# 1-Schematic_CessnaCitationX_Main_ESP32.net
KiCad netlist of a schematic drawn in EasyEDA
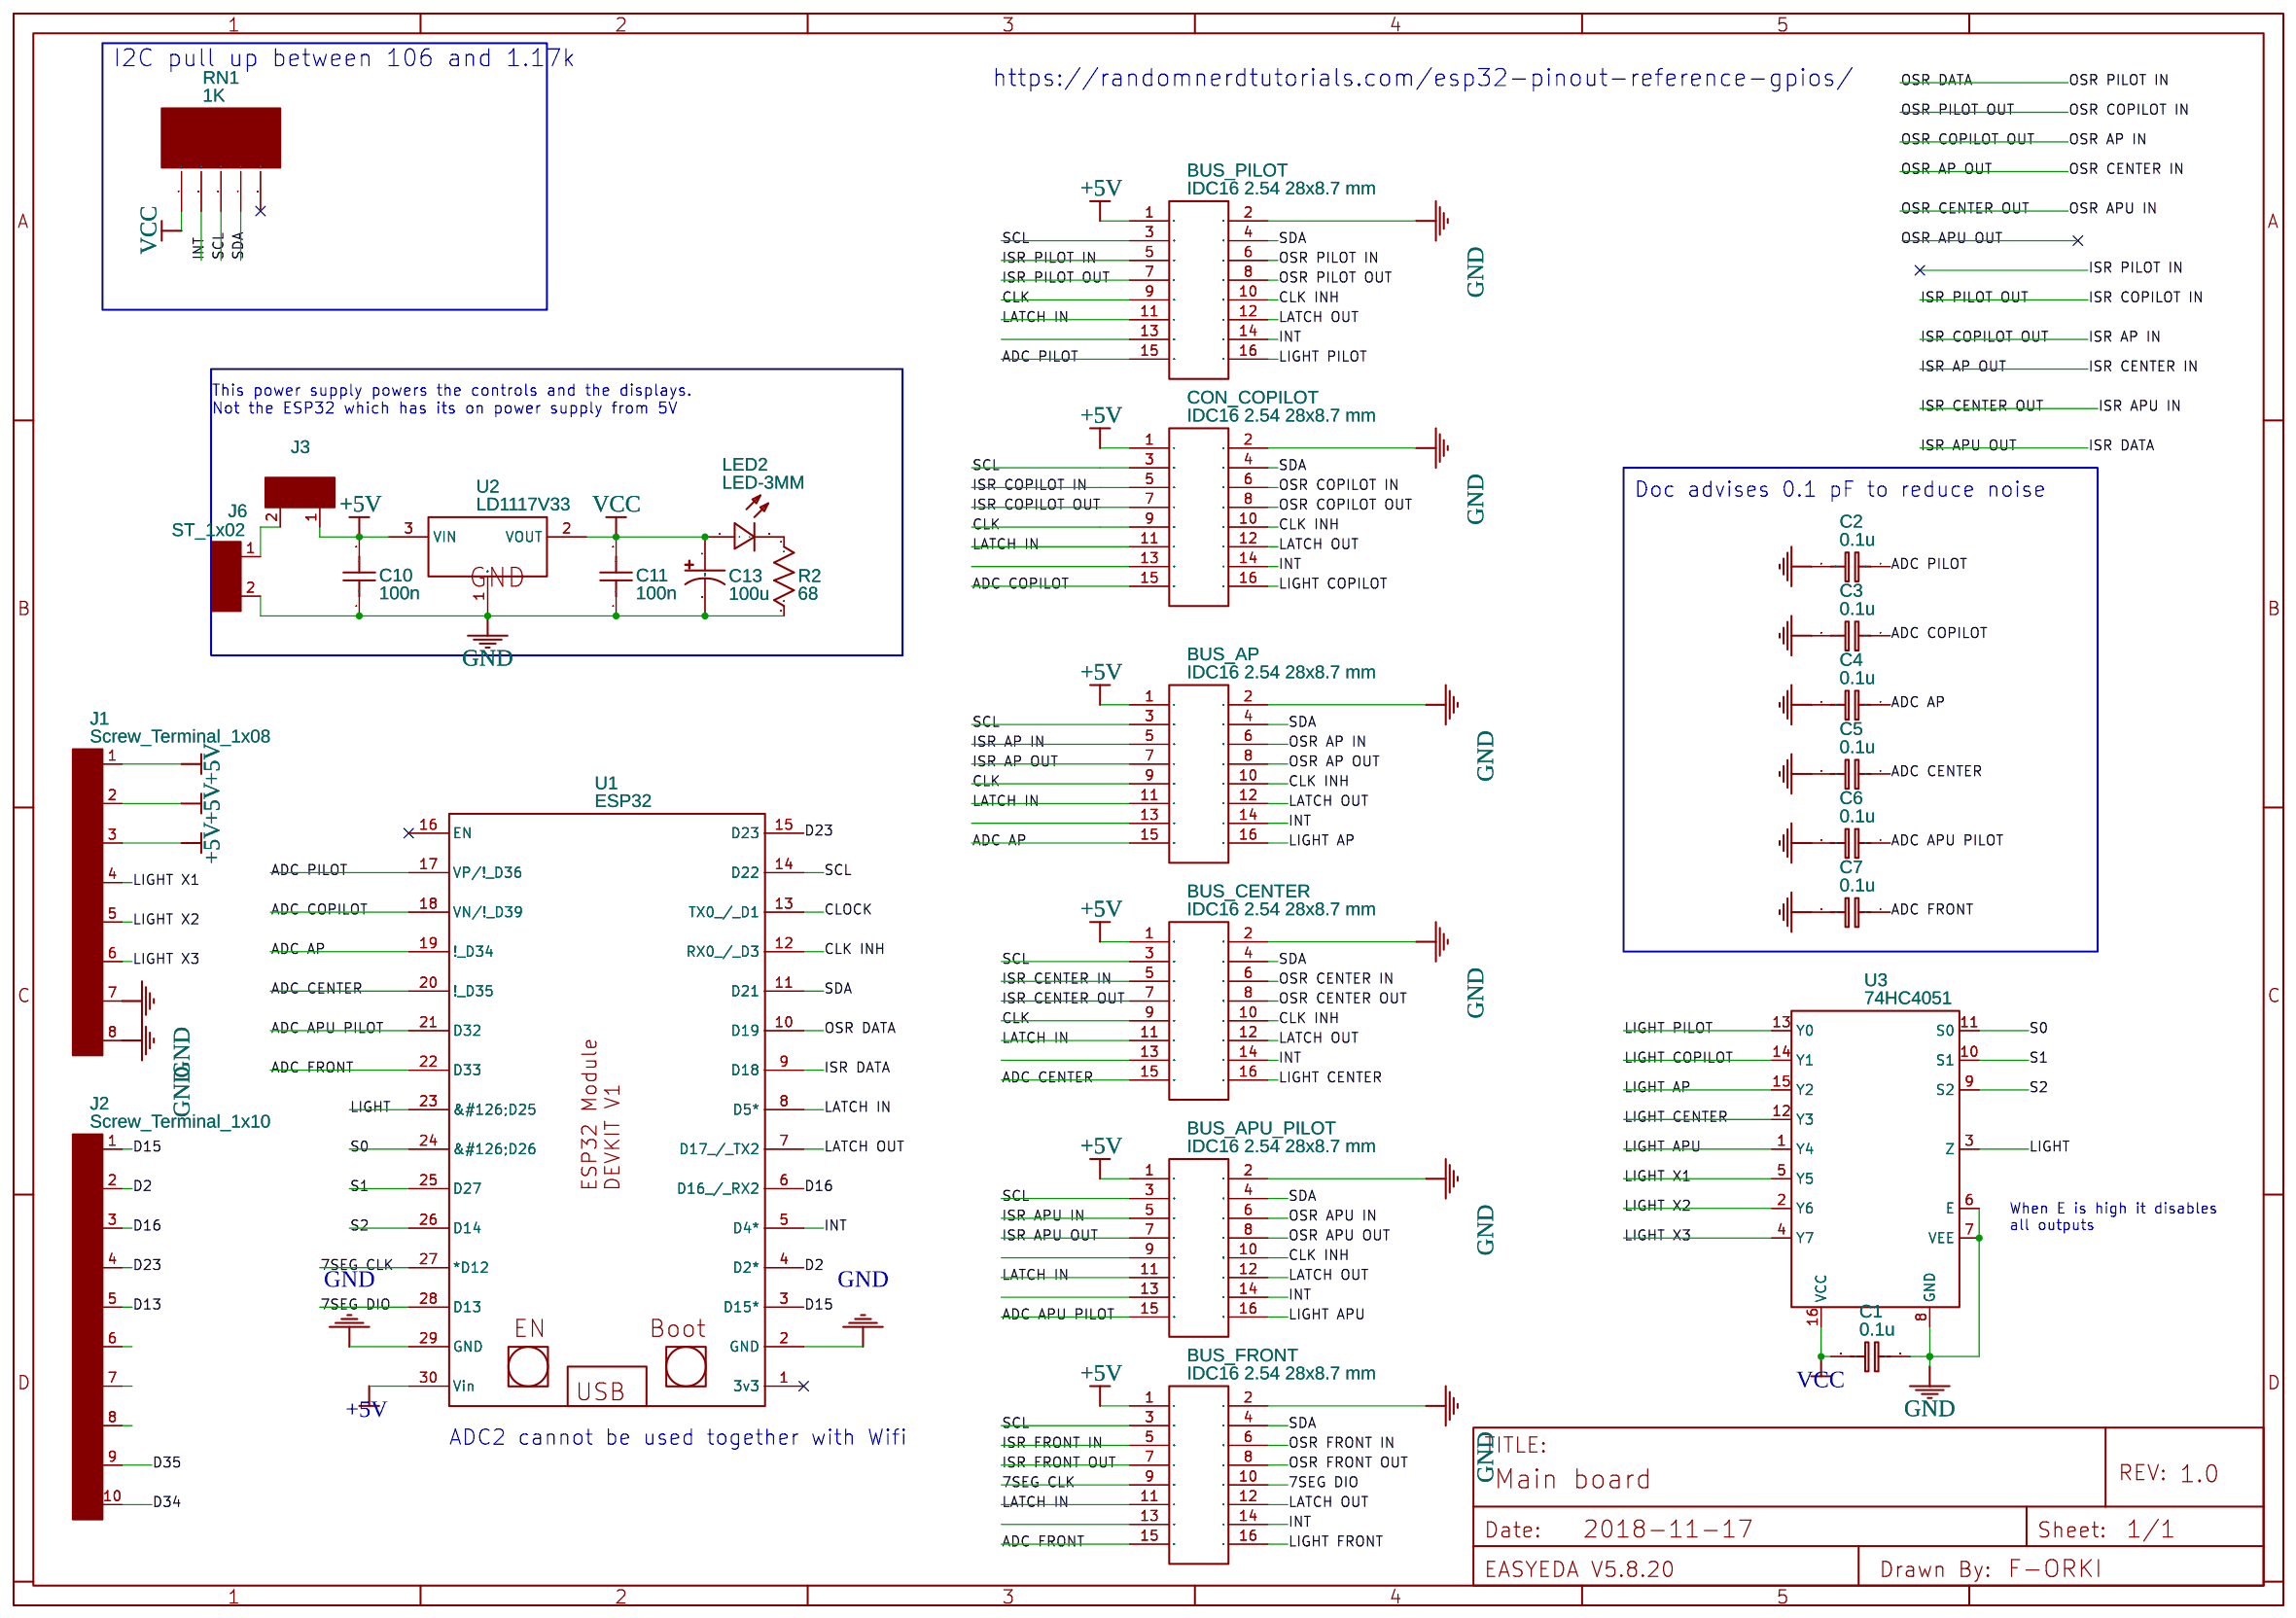
[diagram p0: schematic sheet]

(export (version "E")
  (design (tool "Eeschema 10.0.6"))
  (components
    (comp (ref "BUS_AP")
      (value "IDC16 2.54 28x8.7 mm")
      (fields (field (name "BOM_Manufacturer Part") "?"))
      (libsource (lib "") (part "Unknown_565_430"))
    )
    (comp (ref "BUS_APU_PILOT")
      (value "IDC16 2.54 28x8.7 mm")
      (fields (field (name "BOM_Manufacturer Part") "?"))
      (libsource (lib "") (part "Unknown_565_670"))
    )
    (comp (ref "BUS_CENTER")
      (value "IDC16 2.54 28x8.7 mm")
      (fields (field (name "BOM_Manufacturer Part") "?"))
      (libsource (lib "") (part "Unknown_565_550"))
    )
    (comp (ref "BUS_FRONT")
      (value "IDC16 2.54 28x8.7 mm")
      (fields (field (name "BOM_Manufacturer Part") "?"))
      (libsource (lib "") (part "Unknown_565_785"))
    )
    (comp (ref "BUS_PILOT")
      (value "IDC16 2.54 28x8.7 mm")
      (fields (field (name "BOM_Manufacturer Part") "?"))
      (libsource (lib "") (part "Unknown_565_185"))
    )
    (comp (ref "C1")
      (value "0.1u")
      (fields (field (name "BOM_Manufacturer Part") "?"))
      (libsource (lib "") (part "Cap_RAD-0.1_EU"))
    )
    (comp (ref "C2")
      (value "0.1u")
      (fields (field (name "BOM_Manufacturer Part") "?"))
      (libsource (lib "") (part "Cap_RAD-0.1_EU_1"))
    )
    (comp (ref "C3")
      (value "0.1u")
      (fields (field (name "BOM_Manufacturer Part") "?"))
      (libsource (lib "") (part "Cap_RAD-0.1_EU_1"))
    )
    (comp (ref "C4")
      (value "0.1u")
      (fields (field (name "BOM_Manufacturer Part") "?"))
      (libsource (lib "") (part "Cap_RAD-0.1_EU_1"))
    )
    (comp (ref "C5")
      (value "0.1u")
      (fields (field (name "BOM_Manufacturer Part") "?"))
      (libsource (lib "") (part "Cap_RAD-0.1_EU_1"))
    )
    (comp (ref "C6")
      (value "0.1u")
      (fields (field (name "BOM_Manufacturer Part") "?"))
      (libsource (lib "") (part "Cap_RAD-0.1_EU_1"))
    )
    (comp (ref "C7")
      (value "0.1u")
      (fields (field (name "BOM_Manufacturer Part") "?"))
      (libsource (lib "") (part "Cap_RAD-0.1_EU_1"))
    )
    (comp (ref "C10")
      (value "100n")
      (fields (field (name "BOM_Manufacturer Part") "?"))
      (libsource (lib "") (part "Cap_RAD-0.1_US"))
    )
    (comp (ref "C11")
      (value "100n")
      (fields (field (name "BOM_Manufacturer Part") "?"))
      (libsource (lib "") (part "Cap_RAD-0.1_US"))
    )
    (comp (ref "C13")
      (value "100u")
      (fields (field (name "BOM_Manufacturer Part") "?"))
      (libsource (lib "") (part "Cap_Electrolytic(TH)_D3.0XF1.5_US"))
    )
    (comp (ref "CON_COPILOT")
      (value "IDC16 2.54 28x8.7 mm")
      (fields (field (name "BOM_Manufacturer Part") "?"))
      (libsource (lib "") (part "Unknown_565_300"))
    )
    (comp (ref "J1")
      (value "Screw_Terminal_1x08")
      (fields (field (name "BOM_Manufacturer Part") "?"))
      (libsource (lib "") (part "Unknown_45_450"))
    )
    (comp (ref "J2")
      (value "Screw_Terminal_1x10")
      (fields (field (name "BOM_Manufacturer Part") "?"))
      (libsource (lib "") (part "Unknown_45_665"))
    )
    (comp (ref "J3")
      (value "ST_1x02")
      (fields (field (name "BOM_Manufacturer Part") "?"))
      (libsource (lib "") (part "Unknown_155_250"))
    )
    (comp (ref "J6")
      (value "ST_1x02")
      (fields (field (name "BOM_Manufacturer Part") "?"))
      (libsource (lib "") (part "Unknown_115_275"))
    )
    (comp (ref "LED2")
      (value "LED-3MM")
      (fields
        (field (name "BOM_Manufacturer Part") "204-10SURD/S530-A3")
        (field (name "BOM_Supplier Part") "C99772")
      )
      (libsource (lib "") (part "Unknown_370_260"))
    )
    (comp (ref "R2")
      (value "68")
      (fields (field (name "BOM_Manufacturer Part") "?"))
      (libsource (lib "") (part "Res_AXIAL-0.3(1/8W)_US"))
    )
    (comp (ref "RN1")
      (value "1K")
      (fields (field (name "BOM_Manufacturer Part") "A05-102JP") (field (name "BOM_Supplier Part") "C11389"))
      (libsource (lib "") (part "A05-102JP"))
    )
    (comp (ref "U1")
      (value "ESP32")
      (fields (field (name "BOM_Manufacturer Part") "ESP32 DEV KIT V1"))
      (libsource (lib "") (part "Unknown_300_555"))
    )
    (comp (ref "U2")
      (value "LD1117V33")
      (fields (field (name "BOM_Supplier Part") "C283467"))
      (libsource (lib "") (part "Unknown_240_285"))
    )
    (comp (ref "U3")
      (value "74HC4051")
      (fields (field (name "BOM_Manufacturer Part") "?"))
      (libsource (lib "") (part "Unknown_945_575"))
    )
  )
  (nets
    (net (code "1") (name "+5V") (class "Default")
      (node (ref "BUS_AP") (pin "1") (pinfunction "P1_1") (pintype "unspecified"))
      (node (ref "BUS_APU_PILOT") (pin "1") (pinfunction "P1_1") (pintype "unspecified"))
      (node (ref "BUS_CENTER") (pin "1") (pinfunction "P1_1") (pintype "unspecified"))
      (node (ref "BUS_FRONT") (pin "1") (pinfunction "P1_1") (pintype "unspecified"))
      (node (ref "BUS_PILOT") (pin "1") (pinfunction "P1_1") (pintype "unspecified"))
      (node (ref "C10") (pin "2") (pinfunction "2_2") (pintype "unspecified"))
      (node (ref "CON_COPILOT") (pin "1") (pinfunction "P1_1") (pintype "unspecified"))
      (node (ref "J1") (pin "1") (pintype "unspecified"))
      (node (ref "J1") (pin "2") (pintype "unspecified"))
      (node (ref "J1") (pin "3") (pintype "unspecified"))
      (node (ref "J3") (pin "1") (pintype "unspecified"))
      (node (ref "U1") (pin "30") (pinfunction "Vin_30") (pintype "passive"))
      (node (ref "U2") (pin "3") (pinfunction "VIN_3") (pintype "passive"))
    )
    (net (code "2") (name "/7SEG CLK") (class "Default")
      (node (ref "BUS_FRONT") (pin "9") (pinfunction "P9_9") (pintype "unspecified"))
      (node (ref "U1") (pin "27") (pinfunction "*D12_27") (pintype "unspecified"))
    )
    (net (code "3") (name "/7SEG DIO") (class "Default")
      (node (ref "BUS_FRONT") (pin "10") (pinfunction "P10_10") (pintype "unspecified"))
      (node (ref "U1") (pin "28") (pinfunction "D13_28") (pintype "bidirectional"))
    )
    (net (code "4") (name "/ADC AP") (class "Default")
      (node (ref "BUS_AP") (pin "15") (pinfunction "15_15") (pintype "unspecified"))
      (node (ref "C4") (pin "1") (pinfunction "1_1") (pintype "unspecified"))
      (node (ref "U1") (pin "19") (pinfunction "!_D34_19") (pintype "unspecified"))
    )
    (net (code "5") (name "/ADC APU PILOT") (class "Default")
      (node (ref "BUS_APU_PILOT") (pin "15") (pinfunction "15_15") (pintype "unspecified"))
      (node (ref "C6") (pin "1") (pinfunction "1_1") (pintype "unspecified"))
      (node (ref "U1") (pin "21") (pinfunction "D32_21") (pintype "unspecified"))
    )
    (net (code "6") (name "/ADC CENTER") (class "Default")
      (node (ref "BUS_CENTER") (pin "15") (pinfunction "15_15") (pintype "unspecified"))
      (node (ref "C5") (pin "1") (pinfunction "1_1") (pintype "unspecified"))
      (node (ref "U1") (pin "20") (pinfunction "!_D35_20") (pintype "unspecified"))
    )
    (net (code "7") (name "/ADC COPILOT") (class "Default")
      (node (ref "C3") (pin "1") (pinfunction "1_1") (pintype "unspecified"))
      (node (ref "CON_COPILOT") (pin "15") (pinfunction "15_15") (pintype "unspecified"))
      (node (ref "U1") (pin "18") (pinfunction "VN/!_D39_18") (pintype "unspecified"))
    )
    (net (code "8") (name "/ADC FRONT") (class "Default")
      (node (ref "BUS_FRONT") (pin "15") (pinfunction "15_15") (pintype "unspecified"))
      (node (ref "C7") (pin "1") (pinfunction "1_1") (pintype "unspecified"))
      (node (ref "U1") (pin "22") (pinfunction "D33_22") (pintype "unspecified"))
    )
    (net (code "9") (name "/ADC PILOT") (class "Default")
      (node (ref "BUS_PILOT") (pin "15") (pinfunction "15_15") (pintype "unspecified"))
      (node (ref "C2") (pin "1") (pinfunction "1_1") (pintype "unspecified"))
      (node (ref "U1") (pin "17") (pinfunction "VP/!_D36_17") (pintype "unspecified"))
    )
    (net (code "10") (name "/CLK") (class "Default")
      (node (ref "BUS_AP") (pin "9") (pinfunction "P9_9") (pintype "unspecified"))
      (node (ref "BUS_CENTER") (pin "9") (pinfunction "P9_9") (pintype "unspecified"))
      (node (ref "BUS_PILOT") (pin "9") (pinfunction "P9_9") (pintype "unspecified"))
      (node (ref "CON_COPILOT") (pin "9") (pinfunction "P9_9") (pintype "unspecified"))
    )
    (net (code "11") (name "/CLK INH") (class "Default")
      (node (ref "BUS_AP") (pin "10") (pinfunction "P10_10") (pintype "unspecified"))
      (node (ref "BUS_APU_PILOT") (pin "10") (pinfunction "P10_10") (pintype "unspecified"))
      (node (ref "BUS_CENTER") (pin "10") (pinfunction "P10_10") (pintype "unspecified"))
      (node (ref "BUS_PILOT") (pin "10") (pinfunction "P10_10") (pintype "unspecified"))
      (node (ref "CON_COPILOT") (pin "10") (pinfunction "P10_10") (pintype "unspecified"))
      (node (ref "U1") (pin "12") (pinfunction "RX0_/_D3_12") (pintype "bidirectional"))
    )
    (net (code "12") (name "/CLOCK") (class "Default")
      (node (ref "U1") (pin "13") (pinfunction "TX0_/_D1_13") (pintype "bidirectional"))
    )
    (net (code "13") (name "/D2") (class "Default")
      (node (ref "J2") (pin "2") (pintype "unspecified"))
      (node (ref "U1") (pin "4") (pinfunction "D2*_4") (pintype "bidirectional"))
    )
    (net (code "14") (name "/D13") (class "Default") (node (ref "J2") (pin "5") (pintype "unspecified")))
    (net (code "15") (name "/D15") (class "Default")
      (node (ref "J2") (pin "1") (pintype "unspecified"))
      (node (ref "U1") (pin "3") (pinfunction "D15*_3") (pintype "bidirectional"))
    )
    (net (code "16") (name "/D16") (class "Default")
      (node (ref "J2") (pin "3") (pintype "unspecified"))
      (node (ref "U1") (pin "6") (pinfunction "D16_/_RX2_6") (pintype "bidirectional"))
    )
    (net (code "17") (name "/D23") (class "Default")
      (node (ref "J2") (pin "4") (pintype "unspecified"))
      (node (ref "U1") (pin "15") (pinfunction "D23_15") (pintype "bidirectional"))
    )
    (net (code "18") (name "/D34") (class "Default") (node (ref "J2") (pin "10") (pintype "unspecified")))
    (net (code "19") (name "/D35") (class "Default") (node (ref "J2") (pin "9") (pintype "unspecified")))
    (net (code "20") (name "/INT") (class "Default")
      (node (ref "BUS_AP") (pin "14") (pinfunction "14_14") (pintype "unspecified"))
      (node (ref "BUS_APU_PILOT") (pin "14") (pinfunction "14_14") (pintype "unspecified"))
      (node (ref "BUS_CENTER") (pin "14") (pinfunction "14_14") (pintype "unspecified"))
      (node (ref "BUS_FRONT") (pin "14") (pinfunction "14_14") (pintype "unspecified"))
      (node (ref "BUS_PILOT") (pin "14") (pinfunction "14_14") (pintype "unspecified"))
      (node (ref "CON_COPILOT") (pin "14") (pinfunction "14_14") (pintype "unspecified"))
      (node (ref "RN1") (pin "2") (pinfunction "2_2") (pintype "input"))
      (node (ref "U1") (pin "5") (pinfunction "D4*_5") (pintype "bidirectional"))
    )
    (net (code "21") (name "/ISR AP IN") (class "Default")
      (node (ref "BUS_AP") (pin "5") (pinfunction "P5_5") (pintype "unspecified"))
      (node (ref "CON_COPILOT") (pin "7") (pinfunction "P7_7") (pintype "unspecified"))
    )
    (net (code "22") (name "/ISR AP OUT") (class "Default")
      (node (ref "BUS_AP") (pin "7") (pinfunction "P7_7") (pintype "unspecified"))
      (node (ref "BUS_CENTER") (pin "5") (pinfunction "P5_5") (pintype "unspecified"))
    )
    (net (code "23") (name "/ISR APU IN") (class "Default")
      (node (ref "BUS_APU_PILOT") (pin "5") (pinfunction "P5_5") (pintype "unspecified"))
      (node (ref "BUS_CENTER") (pin "7") (pinfunction "P7_7") (pintype "unspecified"))
    )
    (net (code "24") (name "/ISR APU OUT") (class "Default")
      (node (ref "BUS_APU_PILOT") (pin "7") (pinfunction "P7_7") (pintype "unspecified"))
      (node (ref "U1") (pin "9") (pinfunction "D18_9") (pintype "unspecified"))
    )
    (net (code "25") (name "/ISR COPILOT IN") (class "Default")
      (node (ref "BUS_PILOT") (pin "7") (pinfunction "P7_7") (pintype "unspecified"))
      (node (ref "CON_COPILOT") (pin "5") (pinfunction "P5_5") (pintype "unspecified"))
    )
    (net (code "26") (name "/ISR FRONT IN") (class "Default")
      (node (ref "BUS_FRONT") (pin "5") (pinfunction "P5_5") (pintype "unspecified"))
    )
    (net (code "27") (name "/ISR FRONT OUT") (class "Default")
      (node (ref "BUS_FRONT") (pin "7") (pinfunction "P7_7") (pintype "unspecified"))
    )
    (net (code "28") (name "/ISR PILOT IN") (class "Default")
      (node (ref "BUS_PILOT") (pin "5") (pinfunction "P5_5") (pintype "unspecified"))
    )
    (net (code "29") (name "/LATCH IN") (class "Default")
      (node (ref "BUS_AP") (pin "11") (pinfunction "11_11") (pintype "unspecified"))
      (node (ref "BUS_APU_PILOT") (pin "11") (pinfunction "11_11") (pintype "unspecified"))
      (node (ref "BUS_CENTER") (pin "11") (pinfunction "11_11") (pintype "unspecified"))
      (node (ref "BUS_FRONT") (pin "11") (pinfunction "11_11") (pintype "unspecified"))
      (node (ref "BUS_PILOT") (pin "11") (pinfunction "11_11") (pintype "unspecified"))
      (node (ref "CON_COPILOT") (pin "11") (pinfunction "11_11") (pintype "unspecified"))
      (node (ref "U1") (pin "8") (pinfunction "D5*_8") (pintype "unspecified"))
    )
    (net (code "30") (name "/LATCH OUT") (class "Default")
      (node (ref "BUS_AP") (pin "12") (pinfunction "12_12") (pintype "unspecified"))
      (node (ref "BUS_APU_PILOT") (pin "12") (pinfunction "12_12") (pintype "unspecified"))
      (node (ref "BUS_CENTER") (pin "12") (pinfunction "12_12") (pintype "unspecified"))
      (node (ref "BUS_FRONT") (pin "12") (pinfunction "12_12") (pintype "unspecified"))
      (node (ref "BUS_PILOT") (pin "12") (pinfunction "12_12") (pintype "unspecified"))
      (node (ref "CON_COPILOT") (pin "12") (pinfunction "12_12") (pintype "unspecified"))
      (node (ref "U1") (pin "7") (pinfunction "D17_/_TX2_7") (pintype "bidirectional"))
    )
    (net (code "31") (name "/LIGHT") (class "Default")
      (node (ref "U1") (pin "23") (pinfunction "&#126;D25_23") (pintype "unspecified"))
      (node (ref "U3") (pin "3") (pinfunction "Z_3") (pintype "unspecified"))
    )
    (net (code "32") (name "/LIGHT AP") (class "Default")
      (node (ref "BUS_AP") (pin "16") (pinfunction "16_16") (pintype "unspecified"))
      (node (ref "U3") (pin "15") (pinfunction "Y2_15") (pintype "unspecified"))
    )
    (net (code "33") (name "/LIGHT APU") (class "Default")
      (node (ref "BUS_APU_PILOT") (pin "16") (pinfunction "16_16") (pintype "unspecified"))
      (node (ref "U3") (pin "1") (pinfunction "Y4_1") (pintype "unspecified"))
    )
    (net (code "34") (name "/LIGHT CENTER") (class "Default")
      (node (ref "BUS_CENTER") (pin "16") (pinfunction "16_16") (pintype "unspecified"))
      (node (ref "U3") (pin "12") (pinfunction "Y3_12") (pintype "unspecified"))
    )
    (net (code "35") (name "/LIGHT COPILOT") (class "Default")
      (node (ref "CON_COPILOT") (pin "16") (pinfunction "16_16") (pintype "unspecified"))
      (node (ref "U3") (pin "14") (pinfunction "Y1_14") (pintype "unspecified"))
    )
    (net (code "36") (name "/LIGHT FRONT") (class "Default")
      (node (ref "BUS_FRONT") (pin "16") (pinfunction "16_16") (pintype "unspecified"))
    )
    (net (code "37") (name "/LIGHT PILOT") (class "Default")
      (node (ref "BUS_PILOT") (pin "16") (pinfunction "16_16") (pintype "unspecified"))
      (node (ref "U3") (pin "13") (pinfunction "Y0_13") (pintype "unspecified"))
    )
    (net (code "38") (name "/LIGHT X1") (class "Default")
      (node (ref "J1") (pin "4") (pintype "unspecified"))
      (node (ref "U3") (pin "5") (pinfunction "Y5_5") (pintype "unspecified"))
    )
    (net (code "39") (name "/LIGHT X2") (class "Default")
      (node (ref "J1") (pin "5") (pintype "unspecified"))
      (node (ref "U3") (pin "2") (pinfunction "Y6_2") (pintype "unspecified"))
    )
    (net (code "40") (name "/LIGHT X3") (class "Default")
      (node (ref "J1") (pin "6") (pintype "unspecified"))
      (node (ref "U3") (pin "4") (pinfunction "Y7_4") (pintype "unspecified"))
    )
    (net (code "41") (name "/OSR AP IN") (class "Default")
      (node (ref "BUS_AP") (pin "6") (pinfunction "P6_6") (pintype "unspecified"))
      (node (ref "CON_COPILOT") (pin "8") (pinfunction "P8_8") (pintype "unspecified"))
    )
    (net (code "42") (name "/OSR AP OUT") (class "Default")
      (node (ref "BUS_AP") (pin "8") (pinfunction "P8_8") (pintype "unspecified"))
      (node (ref "BUS_CENTER") (pin "6") (pinfunction "P6_6") (pintype "unspecified"))
    )
    (net (code "43") (name "/OSR APU IN") (class "Default")
      (node (ref "BUS_APU_PILOT") (pin "6") (pinfunction "P6_6") (pintype "unspecified"))
      (node (ref "BUS_CENTER") (pin "8") (pinfunction "P8_8") (pintype "unspecified"))
    )
    (net (code "44") (name "/OSR APU OUT") (class "Default")
      (node (ref "BUS_APU_PILOT") (pin "8") (pinfunction "P8_8") (pintype "unspecified"))
    )
    (net (code "45") (name "/OSR COPILOT IN") (class "Default")
      (node (ref "BUS_PILOT") (pin "8") (pinfunction "P8_8") (pintype "unspecified"))
      (node (ref "CON_COPILOT") (pin "6") (pinfunction "P6_6") (pintype "unspecified"))
    )
    (net (code "46") (name "/OSR DATA") (class "Default")
      (node (ref "BUS_PILOT") (pin "6") (pinfunction "P6_6") (pintype "unspecified"))
      (node (ref "U1") (pin "10") (pinfunction "D19_10") (pintype "bidirectional"))
    )
    (net (code "47") (name "/OSR FRONT IN") (class "Default")
      (node (ref "BUS_FRONT") (pin "6") (pinfunction "P6_6") (pintype "unspecified"))
    )
    (net (code "48") (name "/OSR FRONT OUT") (class "Default")
      (node (ref "BUS_FRONT") (pin "8") (pinfunction "P8_8") (pintype "unspecified"))
    )
    (net (code "49") (name "/S0") (class "Default")
      (node (ref "U1") (pin "24") (pinfunction "&#126;D26_24") (pintype "unspecified"))
      (node (ref "U3") (pin "11") (pinfunction "S0_11") (pintype "unspecified"))
    )
    (net (code "50") (name "/S1") (class "Default")
      (node (ref "U1") (pin "25") (pinfunction "D27_25") (pintype "unspecified"))
      (node (ref "U3") (pin "10") (pinfunction "S1_10") (pintype "unspecified"))
    )
    (net (code "51") (name "/S2") (class "Default")
      (node (ref "U1") (pin "26") (pinfunction "D14_26") (pintype "unspecified"))
      (node (ref "U3") (pin "9") (pinfunction "S2_9") (pintype "unspecified"))
    )
    (net (code "52") (name "/SCL") (class "Default")
      (node (ref "BUS_AP") (pin "3") (pinfunction "P3_3") (pintype "unspecified"))
      (node (ref "BUS_APU_PILOT") (pin "3") (pinfunction "P3_3") (pintype "unspecified"))
      (node (ref "BUS_CENTER") (pin "3") (pinfunction "P3_3") (pintype "unspecified"))
      (node (ref "BUS_FRONT") (pin "3") (pinfunction "P3_3") (pintype "unspecified"))
      (node (ref "BUS_PILOT") (pin "3") (pinfunction "P3_3") (pintype "unspecified"))
      (node (ref "CON_COPILOT") (pin "3") (pinfunction "P3_3") (pintype "unspecified"))
      (node (ref "RN1") (pin "3") (pinfunction "3_3") (pintype "input"))
      (node (ref "U1") (pin "14") (pinfunction "D22_14") (pintype "bidirectional"))
    )
    (net (code "53") (name "/SDA") (class "Default")
      (node (ref "BUS_AP") (pin "4") (pinfunction "P4_4") (pintype "unspecified"))
      (node (ref "BUS_APU_PILOT") (pin "4") (pinfunction "P4_4") (pintype "unspecified"))
      (node (ref "BUS_CENTER") (pin "4") (pinfunction "P4_4") (pintype "unspecified"))
      (node (ref "BUS_FRONT") (pin "4") (pinfunction "P4_4") (pintype "unspecified"))
      (node (ref "BUS_PILOT") (pin "4") (pinfunction "P4_4") (pintype "unspecified"))
      (node (ref "CON_COPILOT") (pin "4") (pinfunction "P4_4") (pintype "unspecified"))
      (node (ref "RN1") (pin "4") (pinfunction "4_4") (pintype "input"))
      (node (ref "U1") (pin "11") (pinfunction "D21_11") (pintype "bidirectional"))
    )
    (net (code "54") (name "GND") (class "Default")
      (node (ref "BUS_AP") (pin "2") (pinfunction "P2_2") (pintype "unspecified"))
      (node (ref "BUS_APU_PILOT") (pin "2") (pinfunction "P2_2") (pintype "unspecified"))
      (node (ref "BUS_CENTER") (pin "2") (pinfunction "P2_2") (pintype "unspecified"))
      (node (ref "BUS_FRONT") (pin "2") (pinfunction "P2_2") (pintype "unspecified"))
      (node (ref "BUS_PILOT") (pin "2") (pinfunction "P2_2") (pintype "unspecified"))
      (node (ref "C1") (pin "1") (pinfunction "1_1") (pintype "unspecified"))
      (node (ref "C10") (pin "1") (pinfunction "1_1") (pintype "unspecified"))
      (node (ref "C11") (pin "1") (pinfunction "1_1") (pintype "unspecified"))
      (node (ref "C13") (pin "2") (pinfunction "2_2") (pintype "unspecified"))
      (node (ref "C2") (pin "2") (pinfunction "2_2") (pintype "unspecified"))
      (node (ref "C3") (pin "2") (pinfunction "2_2") (pintype "unspecified"))
      (node (ref "C4") (pin "2") (pinfunction "2_2") (pintype "unspecified"))
      (node (ref "C5") (pin "2") (pinfunction "2_2") (pintype "unspecified"))
      (node (ref "C6") (pin "2") (pinfunction "2_2") (pintype "unspecified"))
      (node (ref "C7") (pin "2") (pinfunction "2_2") (pintype "unspecified"))
      (node (ref "CON_COPILOT") (pin "2") (pinfunction "P2_2") (pintype "unspecified"))
      (node (ref "J1") (pin "7") (pintype "unspecified"))
      (node (ref "J1") (pin "8") (pintype "unspecified"))
      (node (ref "J6") (pin "2") (pintype "unspecified"))
      (node (ref "R2") (pin "2") (pinfunction "2_2") (pintype "unspecified"))
      (node (ref "U1") (pin "2") (pinfunction "GND_2") (pintype "passive"))
      (node (ref "U1") (pin "29") (pinfunction "GND_29") (pintype "passive"))
      (node (ref "U2") (pin "1") (pinfunction "GND_1") (pintype "unspecified"))
      (node (ref "U3") (pin "6") (pinfunction "E_6") (pintype "unspecified"))
      (node (ref "U3") (pin "7") (pinfunction "VEE_7") (pintype "unspecified"))
      (node (ref "U3") (pin "8") (pinfunction "GND_8") (pintype "unspecified"))
    )
    (net (code "55") (name "Net-(J3-Pad2)") (class "Default")
      (node (ref "J3") (pin "2") (pintype "unspecified"))
      (node (ref "J6") (pin "1") (pintype "unspecified"))
    )
    (net (code "56") (name "Net-(LED2--)") (class "Default")
      (node (ref "LED2") (pin "2") (pinfunction "-_2") (pintype "unspecified"))
      (node (ref "R2") (pin "1") (pinfunction "1_1") (pintype "unspecified"))
    )
    (net (code "57") (name "VCC") (class "Default")
      (node (ref "C1") (pin "2") (pinfunction "2_2") (pintype "unspecified"))
      (node (ref "C11") (pin "2") (pinfunction "2_2") (pintype "unspecified"))
      (node (ref "C13") (pin "1") (pinfunction "1_1") (pintype "unspecified"))
      (node (ref "LED2") (pin "1") (pinfunction "+_1") (pintype "unspecified"))
      (node (ref "RN1") (pin "1") (pinfunction "1_1") (pintype "input"))
      (node (ref "U2") (pin "2") (pinfunction "VOUT_2") (pintype "passive"))
      (node (ref "U3") (pin "16") (pinfunction "VCC_16") (pintype "unspecified"))
    )
    (net (code "58") (name "unconnected-(BUS_AP-Pad13)") (class "Default")
      (node (ref "BUS_AP") (pin "13") (pinfunction "13_13") (pintype "unspecified"))
    )
    (net (code "59") (name "unconnected-(BUS_APU_PILOT-P9-Pad9)") (class "Default")
      (node (ref "BUS_APU_PILOT") (pin "9") (pinfunction "P9_9") (pintype "unspecified"))
    )
    (net (code "60") (name "unconnected-(BUS_APU_PILOT-Pad13)") (class "Default")
      (node (ref "BUS_APU_PILOT") (pin "13") (pinfunction "13_13") (pintype "unspecified"))
    )
    (net (code "61") (name "unconnected-(BUS_CENTER-Pad13)") (class "Default")
      (node (ref "BUS_CENTER") (pin "13") (pinfunction "13_13") (pintype "unspecified"))
    )
    (net (code "62") (name "unconnected-(BUS_FRONT-Pad13)") (class "Default")
      (node (ref "BUS_FRONT") (pin "13") (pinfunction "13_13") (pintype "unspecified"))
    )
    (net (code "63") (name "unconnected-(BUS_PILOT-Pad13)") (class "Default")
      (node (ref "BUS_PILOT") (pin "13") (pinfunction "13_13") (pintype "unspecified"))
    )
    (net (code "64") (name "unconnected-(CON_COPILOT-Pad13)") (class "Default")
      (node (ref "CON_COPILOT") (pin "13") (pinfunction "13_13") (pintype "unspecified"))
    )
    (net (code "65") (name "unconnected-(J2-Pad6)") (class "Default")
      (node (ref "J2") (pin "6") (pintype "unspecified"))
    )
    (net (code "66") (name "unconnected-(J2-Pad7)") (class "Default")
      (node (ref "J2") (pin "7") (pintype "unspecified"))
    )
    (net (code "67") (name "unconnected-(J2-Pad8)") (class "Default")
      (node (ref "J2") (pin "8") (pintype "unspecified"))
    )
    (net (code "68") (name "unconnected-(RN1-Pad5)") (class "Default")
      (node (ref "RN1") (pin "5") (pinfunction "5_5") (pintype "input+no_connect"))
    )
    (net (code "69") (name "unconnected-(U1-3v3-Pad1)") (class "Default")
      (node (ref "U1") (pin "1") (pinfunction "3v3_1") (pintype "passive+no_connect"))
    )
    (net (code "70") (name "unconnected-(U1-EN-Pad16)") (class "Default")
      (node (ref "U1") (pin "16") (pinfunction "EN_16") (pintype "unspecified+no_connect"))
    )
  )
)
